# LPCB281_-_RM57_LAUNCH.net
KiCad netlist of a schematic drawn in Altium Designer
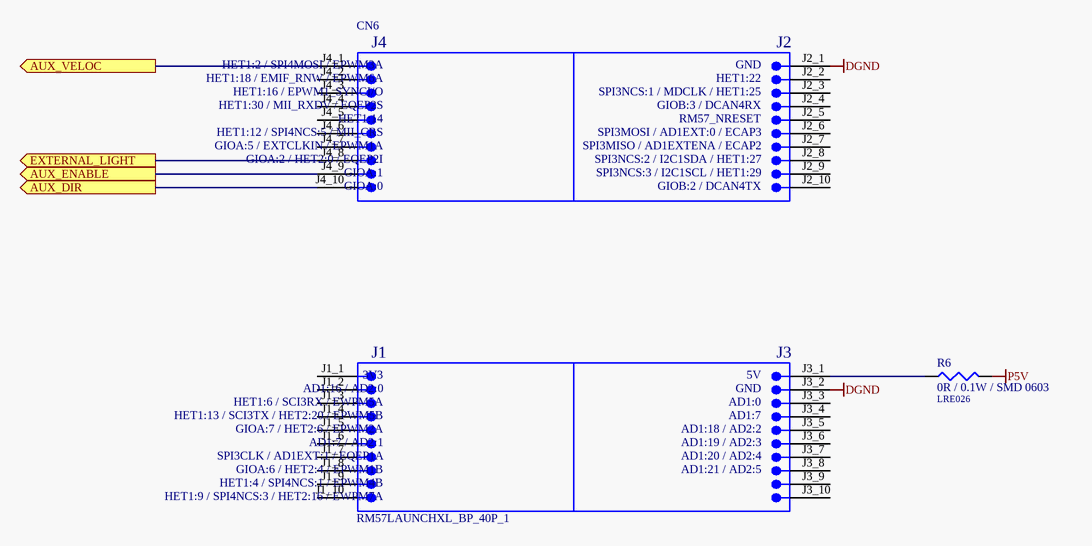
[diagram p0: LPCB281 - RM57 LAUNCH.SchDoc]

(export (version "E")
  (design (tool "Eeschema 10.0.6"))
  (components
    (comp (ref "CN6")
      (value "RM57LAUNCHXL_BP_40P_1")
      (footprint "RM57LAUNCHXL_BP_40P_1")
      (description "Connector, RM57L843 LaunchXL, 40Pin Boosterpack Site1")
      (libsource (lib "LDL_Connectors") (part "RM57LAUNCHXL_BP_40P_1"))
    )
    (comp (ref "R6")
      (value "0R / 0.1W / SMD 0603")
      (footprint "LFP020__CR1608-0603-IPC7351_B")
      (description "Resistor, Ceramic Chip, 0R, 0.1W, SMD 0603 [LRE026]")
      (fields (field (name "LDL_NUMBER") "LRE026"))
      (libsource (lib "LDL_Resistors") (part "0R / 0.1W / SMD 0603"))
    )
  )
  (nets
    (net (code "1") (name "/AUX_DIR") (class "Default") (node (ref "CN6") (pin "J4_10") (pintype "passive")))
    (net (code "2") (name "/AUX_ENABLE") (class "Default")
      (node (ref "CN6") (pin "J4_9") (pintype "passive"))
    )
    (net (code "3") (name "/AUX_VELOC") (class "Default") (node (ref "CN6") (pin "J4_1") (pintype "passive")))
    (net (code "4") (name "/EXTERNAL_LIGHT") (class "Default")
      (node (ref "CN6") (pin "J4_8") (pintype "passive"))
    )
    (net (code "5") (name "DGND") (class "Default")
      (node (ref "CN6") (pin "J2_1") (pintype "passive"))
      (node (ref "CN6") (pin "J3_2") (pintype "passive"))
    )
    (net (code "6") (name "Net-(CN6-PadJ3_1)") (class "Default")
      (node (ref "CN6") (pin "J3_1") (pintype "passive"))
      (node (ref "R6") (pin "1") (pintype "passive"))
    )
    (net (code "7") (name "P5V") (class "Default") (node (ref "R6") (pin "2") (pintype "passive")))
    (net (code "8") (name "unconnected-(CN6-PadJ1_1)") (class "Default")
      (node (ref "CN6") (pin "J1_1") (pintype "passive"))
    )
    (net (code "9") (name "unconnected-(CN6-PadJ1_2)") (class "Default")
      (node (ref "CN6") (pin "J1_2") (pintype "passive"))
    )
    (net (code "10") (name "unconnected-(CN6-PadJ1_3)") (class "Default")
      (node (ref "CN6") (pin "J1_3") (pintype "passive"))
    )
    (net (code "11") (name "unconnected-(CN6-PadJ1_4)") (class "Default")
      (node (ref "CN6") (pin "J1_4") (pintype "passive"))
    )
    (net (code "12") (name "unconnected-(CN6-PadJ1_5)") (class "Default")
      (node (ref "CN6") (pin "J1_5") (pintype "passive"))
    )
    (net (code "13") (name "unconnected-(CN6-PadJ1_6)") (class "Default")
      (node (ref "CN6") (pin "J1_6") (pintype "passive"))
    )
    (net (code "14") (name "unconnected-(CN6-PadJ1_7)") (class "Default")
      (node (ref "CN6") (pin "J1_7") (pintype "passive"))
    )
    (net (code "15") (name "unconnected-(CN6-PadJ1_8)") (class "Default")
      (node (ref "CN6") (pin "J1_8") (pintype "passive"))
    )
    (net (code "16") (name "unconnected-(CN6-PadJ1_9)") (class "Default")
      (node (ref "CN6") (pin "J1_9") (pintype "passive"))
    )
    (net (code "17") (name "unconnected-(CN6-PadJ1_10)") (class "Default")
      (node (ref "CN6") (pin "J1_10") (pintype "passive"))
    )
    (net (code "18") (name "unconnected-(CN6-PadJ2_2)") (class "Default")
      (node (ref "CN6") (pin "J2_2") (pintype "passive"))
    )
    (net (code "19") (name "unconnected-(CN6-PadJ2_3)") (class "Default")
      (node (ref "CN6") (pin "J2_3") (pintype "passive"))
    )
    (net (code "20") (name "unconnected-(CN6-PadJ2_4)") (class "Default")
      (node (ref "CN6") (pin "J2_4") (pintype "passive"))
    )
    (net (code "21") (name "unconnected-(CN6-PadJ2_5)") (class "Default")
      (node (ref "CN6") (pin "J2_5") (pintype "passive"))
    )
    (net (code "22") (name "unconnected-(CN6-PadJ2_6)") (class "Default")
      (node (ref "CN6") (pin "J2_6") (pintype "passive"))
    )
    (net (code "23") (name "unconnected-(CN6-PadJ2_7)") (class "Default")
      (node (ref "CN6") (pin "J2_7") (pintype "passive"))
    )
    (net (code "24") (name "unconnected-(CN6-PadJ2_8)") (class "Default")
      (node (ref "CN6") (pin "J2_8") (pintype "passive"))
    )
    (net (code "25") (name "unconnected-(CN6-PadJ2_9)") (class "Default")
      (node (ref "CN6") (pin "J2_9") (pintype "passive"))
    )
    (net (code "26") (name "unconnected-(CN6-PadJ2_10)") (class "Default")
      (node (ref "CN6") (pin "J2_10") (pintype "passive"))
    )
    (net (code "27") (name "unconnected-(CN6-PadJ3_3)") (class "Default")
      (node (ref "CN6") (pin "J3_3") (pintype "passive"))
    )
    (net (code "28") (name "unconnected-(CN6-PadJ3_4)") (class "Default")
      (node (ref "CN6") (pin "J3_4") (pintype "passive"))
    )
    (net (code "29") (name "unconnected-(CN6-PadJ3_5)") (class "Default")
      (node (ref "CN6") (pin "J3_5") (pintype "passive"))
    )
    (net (code "30") (name "unconnected-(CN6-PadJ3_6)") (class "Default")
      (node (ref "CN6") (pin "J3_6") (pintype "passive"))
    )
    (net (code "31") (name "unconnected-(CN6-PadJ3_7)") (class "Default")
      (node (ref "CN6") (pin "J3_7") (pintype "passive"))
    )
    (net (code "32") (name "unconnected-(CN6-PadJ3_8)") (class "Default")
      (node (ref "CN6") (pin "J3_8") (pintype "passive"))
    )
    (net (code "33") (name "unconnected-(CN6-PadJ3_9)") (class "Default")
      (node (ref "CN6") (pin "J3_9") (pintype "passive"))
    )
    (net (code "34") (name "unconnected-(CN6-PadJ3_10)") (class "Default")
      (node (ref "CN6") (pin "J3_10") (pintype "passive"))
    )
    (net (code "35") (name "unconnected-(CN6-PadJ4_2)") (class "Default")
      (node (ref "CN6") (pin "J4_2") (pintype "passive"))
    )
    (net (code "36") (name "unconnected-(CN6-PadJ4_3)") (class "Default")
      (node (ref "CN6") (pin "J4_3") (pintype "passive"))
    )
    (net (code "37") (name "unconnected-(CN6-PadJ4_4)") (class "Default")
      (node (ref "CN6") (pin "J4_4") (pintype "passive"))
    )
    (net (code "38") (name "unconnected-(CN6-PadJ4_5)") (class "Default")
      (node (ref "CN6") (pin "J4_5") (pintype "passive"))
    )
    (net (code "39") (name "unconnected-(CN6-PadJ4_6)") (class "Default")
      (node (ref "CN6") (pin "J4_6") (pintype "passive"))
    )
    (net (code "40") (name "unconnected-(CN6-PadJ4_7)") (class "Default")
      (node (ref "CN6") (pin "J4_7") (pintype "passive"))
    )
  )
)
